# Scoop.net
KiCad netlist of a schematic drawn in EAGLE
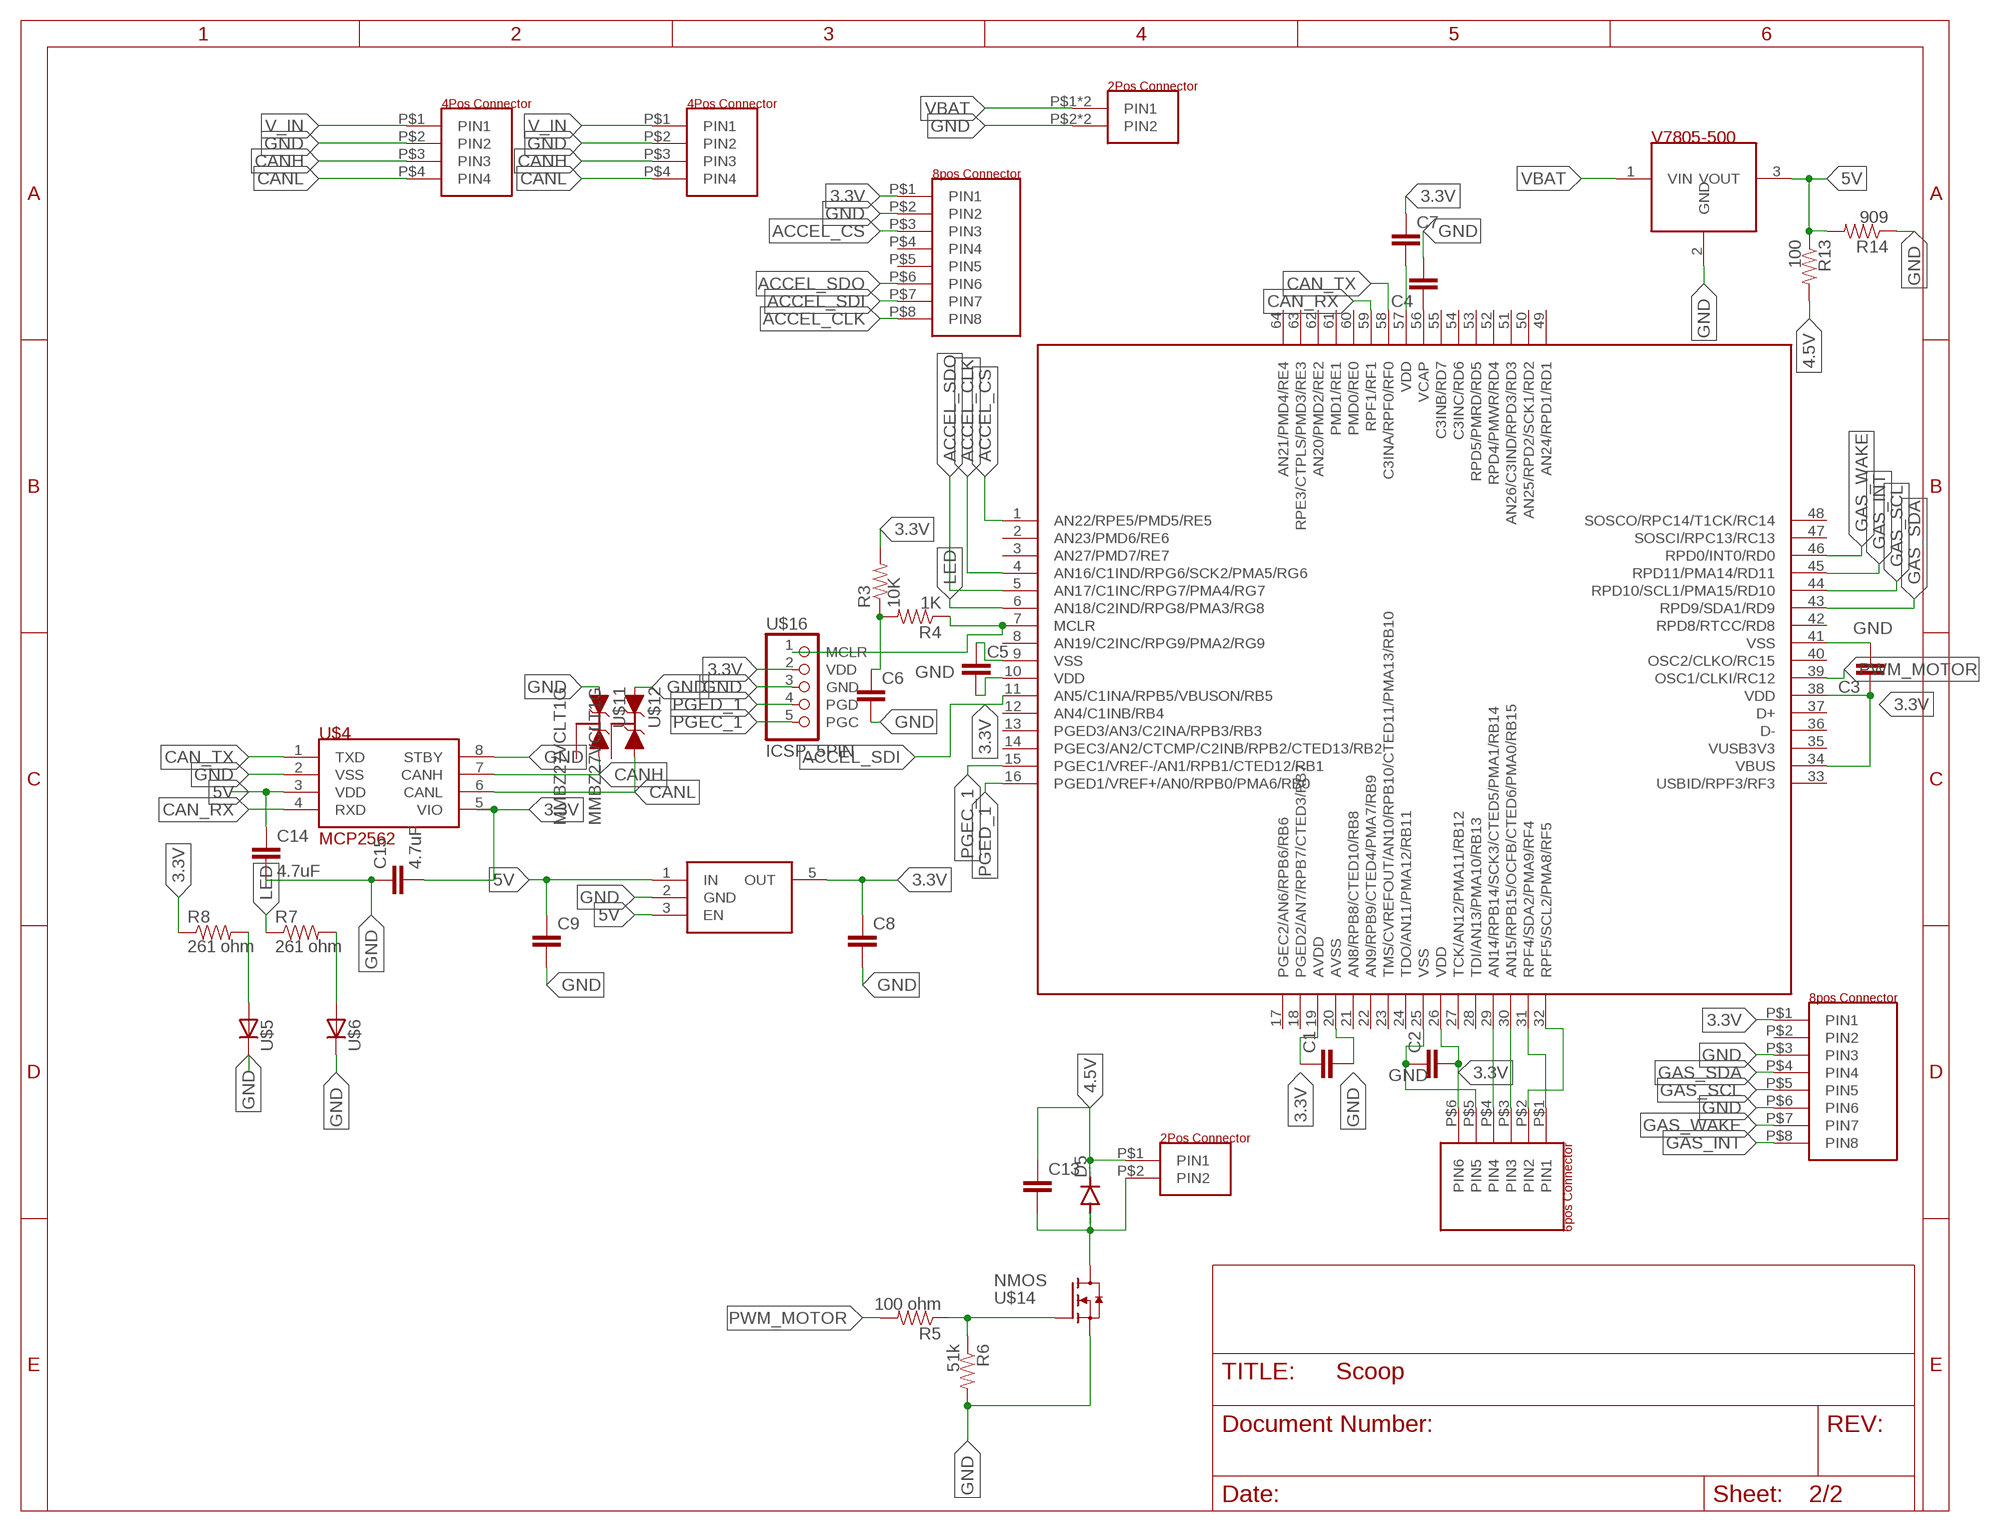
[diagram p0: schematic, sheet 2]

(export (version "E")
  (design (tool "Eeschema 10.0.6"))
  (components
    (comp (ref "C1")
      (value "0.1uF")
      (footprint "eagle-import:0603")
      (libsource (lib "eagle-import") (part "CAP-0603"))
    )
    (comp (ref "C2")
      (value "0.1uF")
      (footprint "eagle-import:0603")
      (libsource (lib "eagle-import") (part "CAP-0603"))
    )
    (comp (ref "C3")
      (value "0.1uF")
      (footprint "eagle-import:0603")
      (libsource (lib "eagle-import") (part "CAP-0603"))
    )
    (comp (ref "C4")
      (value "10uF")
      (footprint "eagle-import:1206")
      (libsource (lib "eagle-import") (part "CAP-1206"))
    )
    (comp (ref "C5")
      (value "0.1uF")
      (footprint "eagle-import:0603")
      (libsource (lib "eagle-import") (part "CAP-0603"))
    )
    (comp (ref "C6")
      (value "0.1uF")
      (footprint "eagle-import:0603")
      (libsource (lib "eagle-import") (part "CAP-0603"))
    )
    (comp (ref "C7")
      (value "0.1uF")
      (footprint "eagle-import:0603")
      (libsource (lib "eagle-import") (part "CAP-0603"))
    )
    (comp (ref "C8")
      (value "1uF")
      (footprint "eagle-import:0603")
      (libsource (lib "eagle-import") (part "CAP-0603"))
    )
    (comp (ref "C9")
      (value "1uF")
      (footprint "eagle-import:0603")
      (libsource (lib "eagle-import") (part "CAP-0603"))
    )
    (comp (ref "C13")
      (value "0.1uF")
      (footprint "eagle-import:0603")
      (libsource (lib "eagle-import") (part "CAP-0603"))
    )
    (comp (ref "C14")
      (value "4.7uF")
      (footprint "eagle-import:0603")
      (libsource (lib "eagle-import") (part "CAP-0603"))
    )
    (comp (ref "C15")
      (value "4.7uF")
      (footprint "eagle-import:0603")
      (libsource (lib "eagle-import") (part "CAP-0603"))
    )
    (comp (ref "D5")
      (value "DIODE-SOD123")
      (footprint "eagle-import:SOD123")
      (libsource (lib "eagle-import") (part "DIODE-SOD123"))
    )
    (comp (ref "R3")
      (value "10K")
      (footprint "eagle-import:0603")
      (libsource (lib "eagle-import") (part "1.8MOHM"))
    )
    (comp (ref "R4")
      (value "1K")
      (footprint "eagle-import:0603")
      (libsource (lib "eagle-import") (part "1.8MOHM"))
    )
    (comp (ref "R5")
      (value "100 ohm")
      (footprint "eagle-import:0603")
      (libsource (lib "eagle-import") (part "1.8MOHM"))
    )
    (comp (ref "R6")
      (value "51k")
      (footprint "eagle-import:0603")
      (libsource (lib "eagle-import") (part "1.8MOHM"))
    )
    (comp (ref "R7")
      (value "261 ohm")
      (footprint "eagle-import:0603")
      (libsource (lib "eagle-import") (part "1.8MOHM"))
    )
    (comp (ref "R8")
      (value "261 ohm")
      (footprint "eagle-import:0603")
      (libsource (lib "eagle-import") (part "1.8MOHM"))
    )
    (comp (ref "R13")
      (value "100")
      (footprint "eagle-import:0603")
      (libsource (lib "eagle-import") (part "1.8MOHM"))
    )
    (comp (ref "R14")
      (value "909")
      (footprint "eagle-import:0603")
      (libsource (lib "eagle-import") (part "1.8MOHM"))
    )
    (comp (ref "U$1")
      (value "PIC32MX530F128H\"")
      (footprint "eagle-import:QFP50P1200X1200X120-64")
      (libsource (lib "eagle-import") (part "PIC32MX530F128H{dblquote}"))
    )
    (comp (ref "U$2")
      (value "2POS_CONNECTOR,1X2_45A_POWERPOLE")
      (footprint "eagle-import:POWERPOLE_45A_1X2")
      (libsource (lib "eagle-import") (part "2POS_CONNECTOR,1X2_45A_POWERPOLE"))
    )
    (comp (ref "U$4")
      (value "MCP2562")
      (footprint "eagle-import:SOIC8")
      (libsource (lib "eagle-import") (part "MCP2562"))
    )
    (comp (ref "U$5")
      (value "LED0603")
      (footprint "eagle-import:DO0603")
      (libsource (lib "eagle-import") (part "LED0603"))
    )
    (comp (ref "U$6")
      (value "LED0603")
      (footprint "eagle-import:DO0603")
      (libsource (lib "eagle-import") (part "LED0603"))
    )
    (comp (ref "U$7")
      (value "2POS_CONNECTOR,.1\"HEADER")
      (footprint "eagle-import:2POS_HEADER_.1_")
      (libsource (lib "eagle-import") (part "2POS_CONNECTOR,.1{dblquote}HEADER"))
    )
    (comp (ref "U$8")
      (value "V7805-500")
      (footprint "eagle-import:SIP3")
      (libsource (lib "eagle-import") (part "V7805-500"))
    )
    (comp (ref "U$9")
      (value "TLV70233DBVR")
      (footprint "eagle-import:SOT-23-5")
      (libsource (lib "eagle-import") (part "TLV70233DBVR"))
    )
    (comp (ref "U$10")
      (value "8POS_CONNECTOR")
      (footprint "eagle-import:8POS_XH_TOP")
      (libsource (lib "eagle-import") (part "8POS_CONNECTOR"))
    )
    (comp (ref "U$11")
      (value "MMBZ27VCLT1G")
      (footprint "eagle-import:SOT23")
      (libsource (lib "eagle-import") (part "MMBZ27VCLT1G"))
    )
    (comp (ref "U$12")
      (value "MMBZ27VCLT1G")
      (footprint "eagle-import:SOT23")
      (libsource (lib "eagle-import") (part "MMBZ27VCLT1G"))
    )
    (comp (ref "U$13")
      (value "6POS_CONNECTOR.1\"PITCH_HEADERS")
      (footprint "eagle-import:6POS_HEADER_.1_")
      (libsource (lib "eagle-import") (part "6POS_CONNECTOR.1{dblquote}PITCH_HEADERS"))
    )
    (comp (ref "U$14")
      (value "NMOS")
      (footprint "eagle-import:SOT95P237X111-3N")
      (libsource (lib "eagle-import") (part "NMOS"))
    )
    (comp (ref "U$15")
      (value "8POS_CONNECTOR")
      (footprint "eagle-import:8POS_XH_TOP")
      (libsource (lib "eagle-import") (part "8POS_CONNECTOR"))
    )
    (comp (ref "U$16")
      (value "ICSP_5PIN")
      (footprint "eagle-import:ICSP_5")
      (libsource (lib "eagle-import") (part "ICSP_5PIN"))
    )
    (comp (ref "U$18")
      (value "4POS_CONNECTORMOLEX_MICROFIT3.0_RA_4PIN_2ROW")
      (footprint "eagle-import:MOLEX_MICROFIT3.0_0430450400")
      (libsource (lib "eagle-import") (part "4POS_CONNECTORMOLEX_MICROFIT3.0_RA_4PIN_2ROW"))
    )
    (comp (ref "U$19")
      (value "4POS_CONNECTORMOLEX_MICROFIT3.0_RA_4PIN_2ROW")
      (footprint "eagle-import:MOLEX_MICROFIT3.0_0430450400")
      (libsource (lib "eagle-import") (part "4POS_CONNECTORMOLEX_MICROFIT3.0_RA_4PIN_2ROW"))
    )
  )
  (nets
    (net (code "1") (name "3.3V") (class "Default")
      (node (ref "C1") (pin "1") (pinfunction "1_1") (pintype "passive"))
      (node (ref "C15") (pin "2") (pinfunction "2_2") (pintype "passive"))
      (node (ref "C2") (pin "2") (pinfunction "2_2") (pintype "passive"))
      (node (ref "C3") (pin "1") (pinfunction "1_1") (pintype "passive"))
      (node (ref "C5") (pin "2") (pinfunction "2_2") (pintype "passive"))
      (node (ref "C7") (pin "1") (pinfunction "1_1") (pintype "passive"))
      (node (ref "C8") (pin "1") (pinfunction "1_1") (pintype "passive"))
      (node (ref "R3") (pin "2") (pinfunction "2_2") (pintype "passive"))
      (node (ref "R8") (pin "1") (pinfunction "1_1") (pintype "passive"))
      (node (ref "U$1") (pin "10") (pinfunction "VDD_10") (pintype "bidirectional"))
      (node (ref "U$1") (pin "19") (pinfunction "AVDD_19") (pintype "bidirectional"))
      (node (ref "U$1") (pin "26") (pinfunction "VDD_26") (pintype "bidirectional"))
      (node (ref "U$1") (pin "34") (pinfunction "VBUS_34") (pintype "bidirectional"))
      (node (ref "U$1") (pin "38") (pinfunction "VDD_38") (pintype "bidirectional"))
      (node (ref "U$10") (pin "P$1") (pinfunction "PIN1_P$1") (pintype "bidirectional"))
      (node (ref "U$13") (pin "P$6") (pinfunction "PIN6_P$6") (pintype "bidirectional"))
      (node (ref "U$15") (pin "P$1") (pinfunction "PIN1_P$1") (pintype "bidirectional"))
      (node (ref "U$16") (pin "2") (pinfunction "VDD_2") (pintype "passive"))
      (node (ref "U$4") (pin "5") (pinfunction "VIO_5") (pintype "bidirectional"))
      (node (ref "U$9") (pin "5") (pinfunction "OUT_5") (pintype "bidirectional"))
    )
    (net (code "2") (name "4.5V") (class "Default")
      (node (ref "C13") (pin "1") (pinfunction "1_1") (pintype "passive"))
      (node (ref "D5") (pin "C") (pinfunction "C_C") (pintype "passive"))
      (node (ref "R13") (pin "2") (pinfunction "2_2") (pintype "passive"))
      (node (ref "U$7") (pin "P$1") (pinfunction "PIN1_P$1") (pintype "bidirectional"))
    )
    (net (code "3") (name "5V") (class "Default")
      (node (ref "C14") (pin "1") (pinfunction "1_1") (pintype "passive"))
      (node (ref "C9") (pin "1") (pinfunction "1_1") (pintype "passive"))
      (node (ref "R13") (pin "1") (pinfunction "1_1") (pintype "passive"))
      (node (ref "R14") (pin "2") (pinfunction "2_2") (pintype "passive"))
      (node (ref "U$4") (pin "3") (pinfunction "VDD_3") (pintype "power_in"))
      (node (ref "U$8") (pin "3") (pinfunction "VOUT_3") (pintype "bidirectional"))
      (node (ref "U$9") (pin "1") (pinfunction "IN_1") (pintype "bidirectional"))
      (node (ref "U$9") (pin "3") (pinfunction "EN_3") (pintype "bidirectional"))
    )
    (net (code "4") (name "ACCEL_CLK") (class "Default")
      (node (ref "U$1") (pin "4") (pinfunction "AN16/C1IND/RPG6/SCK2/PMA5/RG6_4") (pintype "bidirectional"))
      (node (ref "U$15") (pin "P$8") (pinfunction "PIN8_P$8") (pintype "bidirectional"))
    )
    (net (code "5") (name "ACCEL_CS") (class "Default")
      (node (ref "U$1") (pin "1") (pinfunction "AN22/RPE5/PMD5/RE5_1") (pintype "bidirectional"))
      (node (ref "U$15") (pin "P$3") (pinfunction "PIN3_P$3") (pintype "bidirectional"))
    )
    (net (code "6") (name "ACCEL_SDI") (class "Default")
      (node (ref "U$1") (pin "11") (pinfunction "AN5/C1INA/RPB5/VBUSON/RB5_11") (pintype "bidirectional"))
      (node (ref "U$15") (pin "P$7") (pinfunction "PIN7_P$7") (pintype "bidirectional"))
    )
    (net (code "7") (name "ACCEL_SDO") (class "Default")
      (node (ref "U$1") (pin "5") (pinfunction "AN17/C1INC/RPG7/PMA4/RG7_5") (pintype "bidirectional"))
      (node (ref "U$15") (pin "P$6") (pinfunction "PIN6_P$6") (pintype "bidirectional"))
    )
    (net (code "8") (name "CANH") (class "Default")
      (node (ref "U$11") (pin "2") (pinfunction "A2_2") (pintype "passive"))
      (node (ref "U$18") (pin "P$3") (pinfunction "PIN3_P$3") (pintype "bidirectional"))
      (node (ref "U$19") (pin "P$3") (pinfunction "PIN3_P$3") (pintype "bidirectional"))
      (node (ref "U$4") (pin "7") (pinfunction "CANH_7") (pintype "bidirectional"))
    )
    (net (code "9") (name "CANL") (class "Default")
      (node (ref "U$12") (pin "2") (pinfunction "A2_2") (pintype "passive"))
      (node (ref "U$18") (pin "P$4") (pinfunction "PIN4_P$4") (pintype "bidirectional"))
      (node (ref "U$19") (pin "P$4") (pinfunction "PIN4_P$4") (pintype "bidirectional"))
      (node (ref "U$4") (pin "6") (pinfunction "CANL_6") (pintype "bidirectional"))
    )
    (net (code "10") (name "CAN_RX") (class "Default")
      (node (ref "U$1") (pin "59") (pinfunction "RPF1/RF1_59") (pintype "bidirectional"))
      (node (ref "U$4") (pin "4") (pinfunction "RXD_4") (pintype "input"))
    )
    (net (code "11") (name "CAN_TX") (class "Default")
      (node (ref "U$1") (pin "58") (pinfunction "C3INA/RPF0/RF0_58") (pintype "bidirectional"))
      (node (ref "U$4") (pin "1") (pinfunction "TXD_1") (pintype "output"))
    )
    (net (code "12") (name "GAS_INT") (class "Default")
      (node (ref "U$1") (pin "45") (pinfunction "RPD11/PMA14/RD11_45") (pintype "bidirectional"))
      (node (ref "U$10") (pin "P$8") (pinfunction "PIN8_P$8") (pintype "bidirectional"))
    )
    (net (code "13") (name "GAS_SCL") (class "Default")
      (node (ref "U$1") (pin "44") (pinfunction "RPD10/SCL1/PMA15/RD10_44") (pintype "bidirectional"))
      (node (ref "U$10") (pin "P$5") (pinfunction "PIN5_P$5") (pintype "bidirectional"))
    )
    (net (code "14") (name "GAS_SDA") (class "Default")
      (node (ref "U$1") (pin "43") (pinfunction "RPD9/SDA1/RD9_43") (pintype "bidirectional"))
      (node (ref "U$10") (pin "P$4") (pinfunction "PIN4_P$4") (pintype "bidirectional"))
    )
    (net (code "15") (name "GAS_WAKE") (class "Default")
      (node (ref "U$1") (pin "46") (pinfunction "RPD0/INT0/RD0_46") (pintype "bidirectional"))
      (node (ref "U$10") (pin "P$7") (pinfunction "PIN7_P$7") (pintype "bidirectional"))
    )
    (net (code "16") (name "GND") (class "Default")
      (node (ref "C1") (pin "2") (pinfunction "2_2") (pintype "passive"))
      (node (ref "C14") (pin "2") (pinfunction "2_2") (pintype "passive"))
      (node (ref "C15") (pin "1") (pinfunction "1_1") (pintype "passive"))
      (node (ref "C2") (pin "1") (pinfunction "1_1") (pintype "passive"))
      (node (ref "C3") (pin "2") (pinfunction "2_2") (pintype "passive"))
      (node (ref "C4") (pin "2") (pinfunction "2_2") (pintype "passive"))
      (node (ref "C5") (pin "1") (pinfunction "1_1") (pintype "passive"))
      (node (ref "C6") (pin "2") (pinfunction "2_2") (pintype "passive"))
      (node (ref "C8") (pin "2") (pinfunction "2_2") (pintype "passive"))
      (node (ref "C9") (pin "2") (pinfunction "2_2") (pintype "passive"))
      (node (ref "R14") (pin "1") (pinfunction "1_1") (pintype "passive"))
      (node (ref "R6") (pin "2") (pinfunction "2_2") (pintype "passive"))
      (node (ref "U$1") (pin "20") (pinfunction "AVSS_20") (pintype "bidirectional"))
      (node (ref "U$1") (pin "25") (pinfunction "VSS_25") (pintype "bidirectional"))
      (node (ref "U$1") (pin "41") (pinfunction "VSS_41") (pintype "bidirectional"))
      (node (ref "U$1") (pin "9") (pinfunction "VSS_9") (pintype "bidirectional"))
      (node (ref "U$10") (pin "P$3") (pinfunction "PIN3_P$3") (pintype "bidirectional"))
      (node (ref "U$10") (pin "P$6") (pinfunction "PIN6_P$6") (pintype "bidirectional"))
      (node (ref "U$11") (pin "1") (pinfunction "A1_1") (pintype "passive"))
      (node (ref "U$12") (pin "1") (pinfunction "A1_1") (pintype "passive"))
      (node (ref "U$13") (pin "P$5") (pinfunction "PIN5_P$5") (pintype "bidirectional"))
      (node (ref "U$14") (pin "S") (pinfunction "S_S") (pintype "passive"))
      (node (ref "U$15") (pin "P$2") (pinfunction "PIN2_P$2") (pintype "bidirectional"))
      (node (ref "U$16") (pin "3") (pinfunction "GND_3") (pintype "passive"))
      (node (ref "U$18") (pin "P$2") (pinfunction "PIN2_P$2") (pintype "bidirectional"))
      (node (ref "U$19") (pin "P$2") (pinfunction "PIN2_P$2") (pintype "bidirectional"))
      (node (ref "U$2") (pin "P$2") (pinfunction "PIN2_P$2") (pintype "bidirectional"))
      (node (ref "U$2") (pin "P$6") (pinfunction "PIN2_P$6") (pintype "bidirectional"))
      (node (ref "U$4") (pin "2") (pinfunction "VSS_2") (pintype "power_in"))
      (node (ref "U$4") (pin "8") (pinfunction "STBY_8") (pintype "input"))
      (node (ref "U$5") (pin "2") (pinfunction "C_2") (pintype "passive"))
      (node (ref "U$6") (pin "2") (pinfunction "C_2") (pintype "passive"))
      (node (ref "U$8") (pin "2") (pinfunction "GND_2") (pintype "bidirectional"))
      (node (ref "U$9") (pin "2") (pinfunction "GND_2") (pintype "bidirectional"))
    )
    (net (code "17") (name "LED") (class "Default")
      (node (ref "R7") (pin "1") (pinfunction "1_1") (pintype "passive"))
      (node (ref "U$1") (pin "6") (pinfunction "AN18/C2IND/RPG8/PMA3/RG8_6") (pintype "bidirectional"))
    )
    (net (code "18") (name "Net-(C6-Pad1)") (class "Default")
      (node (ref "C6") (pin "1") (pinfunction "1_1") (pintype "passive"))
      (node (ref "R3") (pin "1") (pinfunction "1_1") (pintype "passive"))
      (node (ref "R4") (pin "2") (pinfunction "2_2") (pintype "passive"))
    )
    (net (code "19") (name "Net-(C7-Pad2)") (class "Default")
      (node (ref "C7") (pin "2") (pinfunction "2_2") (pintype "passive"))
      (node (ref "U$1") (pin "57") (pinfunction "VDD_57") (pintype "bidirectional"))
    )
    (net (code "20") (name "Net-(R5-Pad1)") (class "Default")
      (node (ref "R5") (pin "1") (pinfunction "1_1") (pintype "passive"))
      (node (ref "R6") (pin "1") (pinfunction "1_1") (pintype "passive"))
      (node (ref "U$14") (pin "G") (pinfunction "G_G") (pintype "passive"))
    )
    (net (code "21") (name "Net-(U$1-AN14{slash}RPB14{slash}SCK3{slash}CTED5{slash}PMA1{slash}RB14)") (class "Default")
      (node (ref "U$1") (pin "29") (pinfunction "AN14/RPB14/SCK3/CTED5/PMA1/RB14_29") (pintype "bidirectional"))
      (node (ref "U$13") (pin "P$4") (pinfunction "PIN4_P$4") (pintype "bidirectional"))
    )
    (net (code "22") (name "Net-(U$1-AN15{slash}RPB15{slash}OCFB{slash}CTED6{slash}PMA0{slash}RB15)") (class "Default")
      (node (ref "U$1") (pin "30") (pinfunction "AN15/RPB15/OCFB/CTED6/PMA0/RB15_30") (pintype "bidirectional"))
      (node (ref "U$13") (pin "P$3") (pinfunction "PIN3_P$3") (pintype "bidirectional"))
    )
    (net (code "23") (name "Net-(U$1-MCLR)") (class "Default")
      (node (ref "R4") (pin "1") (pinfunction "1_1") (pintype "passive"))
      (node (ref "U$1") (pin "7") (pinfunction "MCLR_7") (pintype "bidirectional"))
      (node (ref "U$16") (pin "1") (pinfunction "MCLR_1") (pintype "passive"))
    )
    (net (code "24") (name "Net-(U$1-RPF4{slash}SDA2{slash}PMA9{slash}RF4)") (class "Default")
      (node (ref "U$1") (pin "31") (pinfunction "RPF4/SDA2/PMA9/RF4_31") (pintype "bidirectional"))
      (node (ref "U$13") (pin "P$1") (pinfunction "PIN1_P$1") (pintype "bidirectional"))
    )
    (net (code "25") (name "Net-(U$1-RPF5{slash}SCL2{slash}PMA8{slash}RF5)") (class "Default")
      (node (ref "U$1") (pin "32") (pinfunction "RPF5/SCL2/PMA8/RF5_32") (pintype "bidirectional"))
      (node (ref "U$13") (pin "P$2") (pinfunction "PIN2_P$2") (pintype "bidirectional"))
    )
    (net (code "26") (name "Net-(U$1-VCAP)") (class "Default")
      (node (ref "C4") (pin "1") (pinfunction "1_1") (pintype "passive"))
      (node (ref "U$1") (pin "56") (pinfunction "VCAP_56") (pintype "bidirectional"))
    )
    (net (code "27") (name "Net-(U$5-A)") (class "Default")
      (node (ref "R8") (pin "2") (pinfunction "2_2") (pintype "passive"))
      (node (ref "U$5") (pin "1") (pinfunction "A_1") (pintype "passive"))
    )
    (net (code "28") (name "Net-(U$6-A)") (class "Default")
      (node (ref "R7") (pin "2") (pinfunction "2_2") (pintype "passive"))
      (node (ref "U$6") (pin "1") (pinfunction "A_1") (pintype "passive"))
    )
    (net (code "29") (name "Net-(U$7-PIN2)") (class "Default")
      (node (ref "C13") (pin "2") (pinfunction "2_2") (pintype "passive"))
      (node (ref "D5") (pin "A") (pinfunction "A_A") (pintype "passive"))
      (node (ref "U$14") (pin "D") (pinfunction "D_D") (pintype "passive"))
      (node (ref "U$7") (pin "P$2") (pinfunction "PIN2_P$2") (pintype "bidirectional"))
    )
    (net (code "30") (name "PGEC_1") (class "Default")
      (node (ref "U$1") (pin "15") (pinfunction "PGEC1/VREF-/AN1/RPB1/CTED12/RB1_15") (pintype "bidirectional"))
      (node (ref "U$16") (pin "5") (pinfunction "PGC_5") (pintype "passive"))
    )
    (net (code "31") (name "PGED_1") (class "Default")
      (node (ref "U$1") (pin "16") (pinfunction "PGED1/VREF+/AN0/RPB0/PMA6/RB0_16") (pintype "bidirectional"))
      (node (ref "U$16") (pin "4") (pinfunction "PGD_4") (pintype "passive"))
    )
    (net (code "32") (name "PWM_MOTOR") (class "Default")
      (node (ref "R5") (pin "2") (pinfunction "2_2") (pintype "passive"))
      (node (ref "U$1") (pin "39") (pinfunction "OSC1/CLKI/RC12_39") (pintype "bidirectional"))
    )
    (net (code "33") (name "VBAT") (class "Default")
      (node (ref "U$2") (pin "P$1") (pinfunction "PIN1_P$1") (pintype "bidirectional"))
      (node (ref "U$2") (pin "P$5") (pinfunction "PIN1_P$5") (pintype "bidirectional"))
      (node (ref "U$8") (pin "1") (pinfunction "VIN_1") (pintype "bidirectional"))
    )
    (net (code "34") (name "V_IN") (class "Default")
      (node (ref "U$18") (pin "P$1") (pinfunction "PIN1_P$1") (pintype "bidirectional"))
      (node (ref "U$19") (pin "P$1") (pinfunction "PIN1_P$1") (pintype "bidirectional"))
    )
    (net (code "35") (name "unconnected-(U$1-AN4{slash}C1INB{slash}RB4-Pad12)") (class "Default")
      (node (ref "U$1") (pin "12") (pinfunction "AN4/C1INB/RB4_12") (pintype "bidirectional"))
    )
    (net (code "36") (name "unconnected-(U$1-AN8{slash}RPB8{slash}CTED10{slash}RB8-Pad21)") (class "Default")
      (node (ref "U$1") (pin "21") (pinfunction "AN8/RPB8/CTED10/RB8_21") (pintype "bidirectional"))
    )
    (net (code "37") (name "unconnected-(U$1-AN9{slash}RPB9{slash}CTED4{slash}PMA7{slash}RB9-Pad22)") (class "Default")
      (node (ref "U$1") (pin "22") (pinfunction "AN9/RPB9/CTED4/PMA7/RB9_22") (pintype "bidirectional"))
    )
    (net (code "38") (name "unconnected-(U$1-AN19{slash}C2INC{slash}RPG9{slash}PMA2{slash}RG9-Pad8)") (class "Default")
      (node (ref "U$1") (pin "8") (pinfunction "AN19/C2INC/RPG9/PMA2/RG9_8") (pintype "bidirectional"))
    )
    (net (code "39") (name "unconnected-(U$1-AN20{slash}PMD2{slash}RE2-Pad62)") (class "Default")
      (node (ref "U$1") (pin "62") (pinfunction "AN20/PMD2/RE2_62") (pintype "bidirectional"))
    )
    (net (code "40") (name "unconnected-(U$1-AN21{slash}PMD4{slash}RE4-Pad64)") (class "Default")
      (node (ref "U$1") (pin "64") (pinfunction "AN21/PMD4/RE4_64") (pintype "bidirectional"))
    )
    (net (code "41") (name "unconnected-(U$1-AN23{slash}PMD6{slash}RE6-Pad2)") (class "Default")
      (node (ref "U$1") (pin "2") (pinfunction "AN23/PMD6/RE6_2") (pintype "bidirectional"))
    )
    (net (code "42") (name "unconnected-(U$1-AN24{slash}RPD1{slash}RD1-Pad49)") (class "Default")
      (node (ref "U$1") (pin "49") (pinfunction "AN24/RPD1/RD1_49") (pintype "bidirectional"))
    )
    (net (code "43") (name "unconnected-(U$1-AN25{slash}RPD2{slash}SCK1{slash}RD2-Pad50)") (class "Default")
      (node (ref "U$1") (pin "50") (pinfunction "AN25/RPD2/SCK1/RD2_50") (pintype "bidirectional"))
    )
    (net (code "44") (name "unconnected-(U$1-AN26{slash}C3IND{slash}RPD3{slash}RD3-Pad51)") (class "Default")
      (node (ref "U$1") (pin "51") (pinfunction "AN26/C3IND/RPD3/RD3_51") (pintype "bidirectional"))
    )
    (net (code "45") (name "unconnected-(U$1-AN27{slash}PMD7{slash}RE7-Pad3)") (class "Default")
      (node (ref "U$1") (pin "3") (pinfunction "AN27/PMD7/RE7_3") (pintype "bidirectional"))
    )
    (net (code "46") (name "unconnected-(U$1-C3INB{slash}RD7-Pad55)") (class "Default")
      (node (ref "U$1") (pin "55") (pinfunction "C3INB/RD7_55") (pintype "bidirectional"))
    )
    (net (code "47") (name "unconnected-(U$1-C3INC{slash}RD6-Pad54)") (class "Default")
      (node (ref "U$1") (pin "54") (pinfunction "C3INC/RD6_54") (pintype "bidirectional"))
    )
    (net (code "48") (name "unconnected-(U$1-D+-Pad37)") (class "Default")
      (node (ref "U$1") (pin "37") (pinfunction "D+_37") (pintype "bidirectional"))
    )
    (net (code "49") (name "unconnected-(U$1-D--Pad36)") (class "Default")
      (node (ref "U$1") (pin "36") (pinfunction "D-_36") (pintype "bidirectional"))
    )
    (net (code "50") (name "unconnected-(U$1-OSC2{slash}CLKO{slash}RC15-Pad40)") (class "Default")
      (node (ref "U$1") (pin "40") (pinfunction "OSC2/CLKO/RC15_40") (pintype "bidirectional"))
    )
    (net (code "51") (name "unconnected-(U$1-PGEC2{slash}AN6{slash}RPB6{slash}RB6-Pad17)") (class "Default")
      (node (ref "U$1") (pin "17") (pinfunction "PGEC2/AN6/RPB6/RB6_17") (pintype "bidirectional"))
    )
    (net (code "52") (name "unconnected-(U$1-PGEC3{slash}AN2{slash}CTCMP{slash}C2INB{slash}RPB2{slash}CTED13{slash}RB2-Pad14)") (class "Default")
      (node (ref "U$1") (pin "14") (pinfunction "PGEC3/AN2/CTCMP/C2INB/RPB2/CTED13/RB2_14") (pintype "bidirectional"))
    )
    (net (code "53") (name "unconnected-(U$1-PGED2{slash}AN7{slash}RPB7{slash}CTED3{slash}RB7-Pad18)") (class "Default")
      (node (ref "U$1") (pin "18") (pinfunction "PGED2/AN7/RPB7/CTED3/RB7_18") (pintype "bidirectional"))
    )
    (net (code "54") (name "unconnected-(U$1-PGED3{slash}AN3{slash}C2INA{slash}RPB3{slash}RB3-Pad13)") (class "Default")
      (node (ref "U$1") (pin "13") (pinfunction "PGED3/AN3/C2INA/RPB3/RB3_13") (pintype "bidirectional"))
    )
    (net (code "55") (name "unconnected-(U$1-PMD0{slash}RE0-Pad60)") (class "Default")
      (node (ref "U$1") (pin "60") (pinfunction "PMD0/RE0_60") (pintype "bidirectional"))
    )
    (net (code "56") (name "unconnected-(U$1-PMD1{slash}RE1-Pad61)") (class "Default")
      (node (ref "U$1") (pin "61") (pinfunction "PMD1/RE1_61") (pintype "bidirectional"))
    )
    (net (code "57") (name "unconnected-(U$1-RPD4{slash}PMWR{slash}RD4-Pad52)") (class "Default")
      (node (ref "U$1") (pin "52") (pinfunction "RPD4/PMWR/RD4_52") (pintype "bidirectional"))
    )
    (net (code "58") (name "unconnected-(U$1-RPD5{slash}PMRD{slash}RD5-Pad53)") (class "Default")
      (node (ref "U$1") (pin "53") (pinfunction "RPD5/PMRD/RD5_53") (pintype "bidirectional"))
    )
    (net (code "59") (name "unconnected-(U$1-RPD8{slash}RTCC{slash}RD8-Pad42)") (class "Default")
      (node (ref "U$1") (pin "42") (pinfunction "RPD8/RTCC/RD8_42") (pintype "bidirectional"))
    )
    (net (code "60") (name "unconnected-(U$1-RPE3{slash}CTPLS{slash}PMD3{slash}RE3-Pad63)") (class "Default")
      (node (ref "U$1") (pin "63") (pinfunction "RPE3/CTPLS/PMD3/RE3_63") (pintype "bidirectional"))
    )
    (net (code "61") (name "unconnected-(U$1-SOSCI{slash}RPC13{slash}RC13-Pad47)") (class "Default")
      (node (ref "U$1") (pin "47") (pinfunction "SOSCI/RPC13/RC13_47") (pintype "bidirectional"))
    )
    (net (code "62") (name "unconnected-(U$1-SOSCO{slash}RPC14{slash}T1CK{slash}RC14-Pad48)") (class "Default")
      (node (ref "U$1") (pin "48") (pinfunction "SOSCO/RPC14/T1CK/RC14_48") (pintype "bidirectional"))
    )
    (net (code "63") (name "unconnected-(U$1-TCK{slash}AN12{slash}PMA11{slash}RB12-Pad27)") (class "Default")
      (node (ref "U$1") (pin "27") (pinfunction "TCK/AN12/PMA11/RB12_27") (pintype "bidirectional"))
    )
    (net (code "64") (name "unconnected-(U$1-TDI{slash}AN13{slash}PMA10{slash}RB13-Pad28)") (class "Default")
      (node (ref "U$1") (pin "28") (pinfunction "TDI/AN13/PMA10/RB13_28") (pintype "bidirectional"))
    )
    (net (code "65") (name "unconnected-(U$1-TDO{slash}AN11{slash}PMA12{slash}RB11-Pad24)") (class "Default")
      (node (ref "U$1") (pin "24") (pinfunction "TDO/AN11/PMA12/RB11_24") (pintype "bidirectional"))
    )
    (net (code "66") (name "unconnected-(U$1-TMS{slash}CVREFOUT{slash}AN10{slash}RPB10{slash}CTED11{slash}PMA13{slash}RB10-Pad23)") (class "Default")
      (node (ref "U$1") (pin "23") (pinfunction "TMS/CVREFOUT/AN10/RPB10/CTED11/PMA13/RB10_23") (pintype "bidirectional"))
    )
    (net (code "67") (name "unconnected-(U$1-USBID{slash}RPF3{slash}RF3-Pad33)") (class "Default")
      (node (ref "U$1") (pin "33") (pinfunction "USBID/RPF3/RF3_33") (pintype "bidirectional"))
    )
    (net (code "68") (name "unconnected-(U$1-VUSB3V3-Pad35)") (class "Default")
      (node (ref "U$1") (pin "35") (pinfunction "VUSB3V3_35") (pintype "bidirectional"))
    )
    (net (code "69") (name "unconnected-(U$10-PIN2-PadP$2)") (class "Default")
      (node (ref "U$10") (pin "P$2") (pinfunction "PIN2_P$2") (pintype "bidirectional"))
    )
    (net (code "70") (name "unconnected-(U$11-C-Pad3)") (class "Default")
      (node (ref "U$11") (pin "3") (pinfunction "C_3") (pintype "bidirectional"))
    )
    (net (code "71") (name "unconnected-(U$12-C-Pad3)") (class "Default")
      (node (ref "U$12") (pin "3") (pinfunction "C_3") (pintype "bidirectional"))
    )
    (net (code "72") (name "unconnected-(U$15-PIN4-PadP$4)") (class "Default")
      (node (ref "U$15") (pin "P$4") (pinfunction "PIN4_P$4") (pintype "bidirectional"))
    )
    (net (code "73") (name "unconnected-(U$15-PIN5-PadP$5)") (class "Default")
      (node (ref "U$15") (pin "P$5") (pinfunction "PIN5_P$5") (pintype "bidirectional"))
    )
  )
)
